# Power_Distribution_2021_12V.net
KiCad netlist of a schematic drawn in Altium Designer
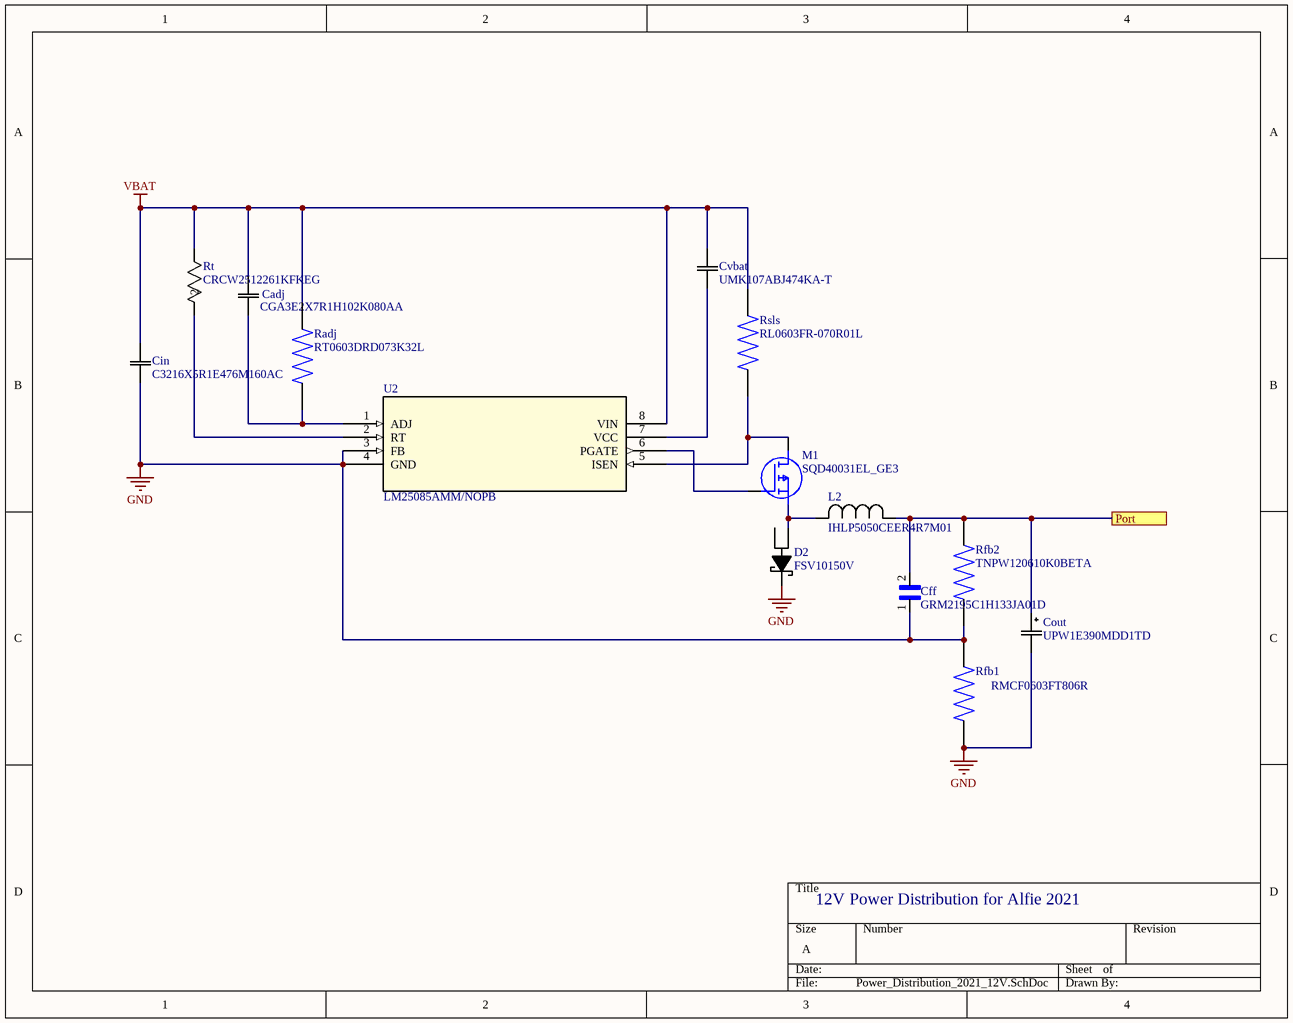
[diagram p0: Power_Distribution_2021_12V.SchDoc]

(export (version "E")
  (design (tool "Eeschema 10.0.6"))
  (components
    (comp (ref "Cadj")
      (value "CGA3E2X7R1H102K080AA")
      (footprint "CAP_1608_TDK")
      (description "CAP CER 1000PF 50V X7R 0603")
      (fields (field (name "COPYRIGHT") "Copyright (C) 2021 Accelerated Designs. All rights reserved"))
      (libsource (lib "Power_Distribution") (part "CGA3E2X7R1H102K080AA"))
    )
    (comp (ref "Cff")
      (value "GRM2195C1H133JA01D")
      (footprint "CAPC2012X95N:CAPC2012X95N")
      (description "SMD Capacitor C0G(EIA) with Capacitance: 13000pF Tol. 5%. Rated Voltage: 50Vdc")
      (libsource (lib "Power_Distribution") (part "GRM2195C1H133JA01D"))
    )
    (comp (ref "Cin")
      (value "C3216X5R1E476M160AC")
      (footprint "CAP_3216_TDK")
      (description "CAP CER 47UF 25V X5R 1206")
      (fields (field (name "COPYRIGHT") "Copyright (C) 2021 Accelerated Designs. All rights reserved"))
      (libsource (lib "Power_Distribution") (part "C3216X5R1E476M160AC"))
    )
    (comp (ref "Cout")
      (value "UPW1E390MDD1TD")
      (footprint "CAP_UEP_5X11_NCH")
      (description "CAP ALUM 39UF 20% 25V RADIAL")
      (fields (field (name "COPYRIGHT") "Copyright (C) 2018 Accelerated Designs. All rights reserved"))
      (libsource (lib "Power_Distribution") (part "UPW1E390MDD1TD"))
    )
    (comp (ref "Cvbat")
      (value "UMK107ABJ474KA-T")
      (footprint "cap_UMK107ABJ474KA-T_TAY")
      (description "CAP CER 0.47UF 50V X5R 0603")
      (fields (field (name "COPYRIGHT") "Copyright (C) 2018 Accelerated Designs. All rights reserved"))
      (libsource (lib "Power_Distribution") (part "UMK107ABJ474KA-T"))
    )
    (comp (ref "D2")
      (value "FSV10150V")
      (footprint "TO-277_3L")
      (description "DIODE SCHOTTKY 150V 10A TO277-3")
      (libsource (lib "Power_Distribution") (part "FSV10150V"))
    )
    (comp (ref "L2")
      (value "IHLP5050CEER4R7M01")
      (footprint "IND_IHLP-5050CE_VIS")
      (description "FIXED IND 4.7UH 10A 15 MOHM SMD")
      (fields (field (name "COPYRIGHT") "Copyright (C) 2021 Accelerated Designs. All rights reserved"))
      (libsource (lib "Power_Distribution") (part "IHLP5050CEER4R7M01"))
    )
    (comp (ref "M1")
      (value "SQD40031EL_GE3")
      (footprint "Power_Distribution:SQD40031EL_GE3")
      (description "MOSFET (P-Channel)")
      (libsource (lib "Power_Distribution") (part "SQD40031EL_GE3"))
    )
    (comp (ref "Radj")
      (value "RT0603DRD073K32L")
      (footprint "RESC1608X55N:RESC1608X55N")
      (description "RES SMD 3.32KOHM 0.5% 1/10W 0603")
      (libsource (lib "Power_Distribution") (part "RT0603DRD073K32L"))
    )
    (comp (ref "Rfb1")
      (value "RMCF0603FT806R")
      (footprint "RESC1508X55N:RESC1508X55N")
      (description "RES 806 OHM 1% 1/10W 0603")
      (libsource (lib "Power_Distribution") (part "RMCF0603FT806R"))
    )
    (comp (ref "Rfb2")
      (value "TNPW120610K0BETA")
      (footprint "RESC3216X65N:RESC3216X65N")
      (description "Res Thin Film 1206 10K Ohm 0.1% 0.25W(1/4W) ?25ppm/C Molded SMD T/R")
      (libsource (lib "Power_Distribution") (part "TNPW120610K0BETA"))
    )
    (comp (ref "Rsls")
      (value "RL0603FR-070R01L")
      (footprint "RESC1608X55N")
      (description ".01 OHM 1% 1/10W")
      (libsource (lib "RL0603FR-070R01L") (part "RL0603FR-070R01L"))
    )
    (comp (ref "Rt")
      (value "CRCW2512261KFKEG")
      (footprint "RC2512N_VIS")
      (description "RES SMD 261K OHM 1% 1W 2512")
      (fields (field (name "COPYRIGHT") "Copyright (C) 2021 Accelerated Designs. All rights reserved"))
      (libsource (lib "Power_Distribution") (part "CRCW2512261KFKEG"))
    )
    (comp (ref "U2")
      (value "LM25085AMM/NOPB")
      (footprint "MUA08A")
      (description "IC REG CTRLR BUCK 8VSSOP")
      (fields (field (name "COPYRIGHT") "Copyright (C) 2021 Accelerated Designs. All rights reserved"))
      (libsource (lib "Power_Distribution") (part "LM25085AMM/NOPB"))
    )
  )
  (nets
    (net (code "1") (name "/Port") (class "Default")
      (node (ref "Cff") (pin "2") (pinfunction "2_2") (pintype "passive"))
      (node (ref "Cout") (pin "1") (pinfunction "1_1") (pintype "passive"))
      (node (ref "L2") (pin "1") (pinfunction "1_1") (pintype "passive"))
      (node (ref "Rfb2") (pin "2") (pinfunction "2_2") (pintype "passive"))
    )
    (net (code "2") (name "GND") (class "Default")
      (node (ref "Cff") (pin "1") (pinfunction "1_1") (pintype "passive"))
      (node (ref "Cin") (pin "1") (pinfunction "1_1") (pintype "passive"))
      (node (ref "Cout") (pin "2") (pinfunction "2_2") (pintype "passive"))
      (node (ref "D2") (pin "2") (pinfunction "2_2") (pintype "passive"))
      (node (ref "Rfb1") (pin "1") (pinfunction "1_1") (pintype "passive"))
      (node (ref "Rfb1") (pin "2") (pinfunction "2_2") (pintype "passive"))
      (node (ref "Rfb2") (pin "1") (pinfunction "1_1") (pintype "passive"))
      (node (ref "U2") (pin "3") (pinfunction "FB_3") (pintype "input"))
      (node (ref "U2") (pin "4") (pinfunction "GND_4") (pintype "power_in"))
    )
    (net (code "3") (name "Net-(M1-D)") (class "Default")
      (node (ref "M1") (pin "3") (pinfunction "D_3") (pintype "passive"))
      (node (ref "Rsls") (pin "1") (pinfunction "1_1") (pintype "passive"))
      (node (ref "U2") (pin "5") (pinfunction "ISEN_5") (pintype "input"))
    )
    (net (code "4") (name "Net-(M1-G)") (class "Default")
      (node (ref "M1") (pin "1") (pinfunction "G_1") (pintype "passive"))
      (node (ref "U2") (pin "6") (pinfunction "PGATE_6") (pintype "output"))
    )
    (net (code "5") (name "Net-(M1-S)") (class "Default")
      (node (ref "D2") (pin "0") (pinfunction "0_0") (pintype "passive"))
      (node (ref "L2") (pin "2") (pinfunction "2_2") (pintype "passive"))
      (node (ref "M1") (pin "2") (pinfunction "S_2") (pintype "passive"))
    )
    (net (code "6") (name "Net-(U2-ADJ)") (class "Default")
      (node (ref "Cadj") (pin "1") (pinfunction "1_1") (pintype "passive"))
      (node (ref "Radj") (pin "1") (pinfunction "1_1") (pintype "passive"))
      (node (ref "U2") (pin "1") (pinfunction "ADJ_1") (pintype "input"))
    )
    (net (code "7") (name "Net-(U2-RT)") (class "Default")
      (node (ref "Rt") (pin "2") (pinfunction "2_2") (pintype "passive"))
      (node (ref "U2") (pin "2") (pinfunction "RT_2") (pintype "input"))
    )
    (net (code "8") (name "Net-(U2-VCC)") (class "Default")
      (node (ref "Cvbat") (pin "2") (pinfunction "2_2") (pintype "passive"))
      (node (ref "U2") (pin "7") (pinfunction "VCC_7") (pintype "power_in"))
    )
    (net (code "9") (name "VBAT") (class "Default")
      (node (ref "Cadj") (pin "2") (pinfunction "2_2") (pintype "passive"))
      (node (ref "Cin") (pin "2") (pinfunction "2_2") (pintype "passive"))
      (node (ref "Cvbat") (pin "1") (pinfunction "1_1") (pintype "passive"))
      (node (ref "Radj") (pin "2") (pinfunction "2_2") (pintype "passive"))
      (node (ref "Rsls") (pin "2") (pinfunction "2_2") (pintype "passive"))
      (node (ref "Rt") (pin "1") (pinfunction "1_1") (pintype "passive"))
      (node (ref "U2") (pin "8") (pinfunction "VIN_8") (pintype "power_in"))
    )
    (net (code "10") (name "unconnected-(D2-Pad1)") (class "Default")
      (node (ref "D2") (pin "1") (pinfunction "1_1") (pintype "passive"))
    )
  )
)
